# 1st_layer.net
KiCad netlist of a schematic drawn in EAGLE
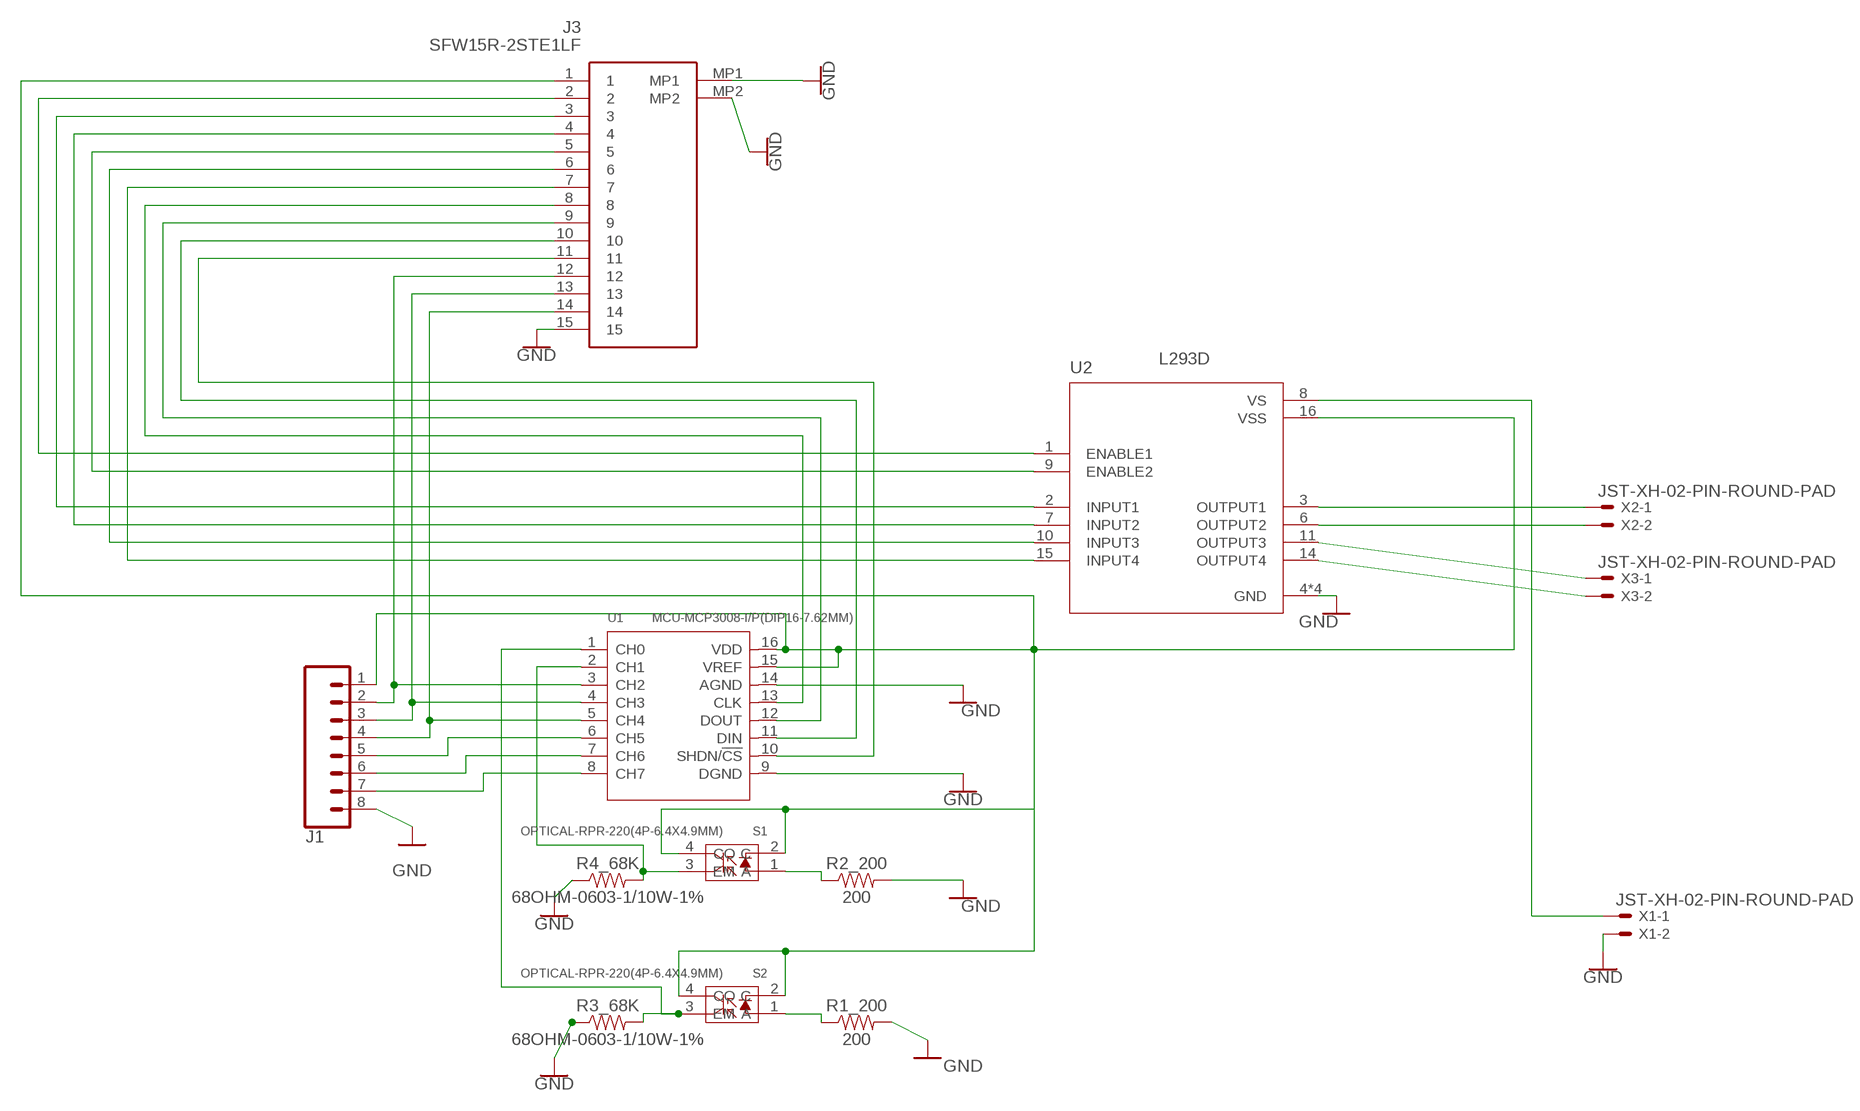
[diagram p0: schematic, sheet 1]

(export (version "E")
  (design (tool "Eeschema 10.0.6"))
  (components
    (comp (ref "J1")
      (value "CONN_08LONGPADS")
      (footprint "eagle-import:1X08_LONGPADS")
      (libsource (lib "eagle-import") (part "CONN_08LONGPADS"))
    )
    (comp (ref "J3")
      (value "SFW15R-2STE1LF")
      (footprint "eagle-import:SFW15R2STE1LF")
      (libsource (lib "eagle-import") (part "SFW15R-2STE1LF"))
    )
    (comp (ref "R1_200")
      (value "200")
      (footprint "eagle-import:0603")
      (libsource (lib "eagle-import") (part "200OHM-0603-1/10W-1%"))
    )
    (comp (ref "R2_200")
      (value "200")
      (footprint "eagle-import:0603")
      (libsource (lib "eagle-import") (part "200OHM-0603-1/10W-1%"))
    )
    (comp (ref "R3_68K")
      (value "68OHM-0603-1/10W-1%")
      (footprint "eagle-import:0603")
      (libsource (lib "eagle-import") (part "68OHM-0603-1/10W-1%"))
    )
    (comp (ref "R4_68K")
      (value "68OHM-0603-1/10W-1%")
      (footprint "eagle-import:0603")
      (libsource (lib "eagle-import") (part "68OHM-0603-1/10W-1%"))
    )
    (comp (ref "S1")
      (value "OPTICAL-RPR-220(4P-6.4X4.9MM)")
      (footprint "eagle-import:SNR4-8.7X4.5X5.8MM")
      (fields
        (field (name "DIGI-KEY_PART_NUMBER") "511-1366-ND")
        (field (name "MF") "Rohm")
        (field (name "MP") "RPR-220")
      )
      (libsource (lib "eagle-import") (part "OPTICAL-RPR-220(4P-6.4X4.9MM)"))
    )
    (comp (ref "S2")
      (value "OPTICAL-RPR-220(4P-6.4X4.9MM)")
      (footprint "eagle-import:SNR4-8.7X4.5X5.8MM")
      (fields
        (field (name "DIGI-KEY_PART_NUMBER") "511-1366-ND")
        (field (name "MF") "Rohm")
        (field (name "MP") "RPR-220")
      )
      (libsource (lib "eagle-import") (part "OPTICAL-RPR-220(4P-6.4X4.9MM)"))
    )
    (comp (ref "U1")
      (value "MCU-MCP3008-I/P(DIP16-7.62MM)")
      (footprint "eagle-import:DIP16-2.54-19.2X7.62MM")
      (fields (field (name "MF") "Microchip") (field (name "MP") "MCP3008-I/P"))
      (libsource (lib "eagle-import") (part "MCU-MCP3008-I/P(DIP16-7.62MM)"))
    )
    (comp (ref "U2")
      (value "L293D")
      (footprint "eagle-import:DIP880W50P254L2000H510Q16")
      (fields (field (name "MF") "STMicroelectronics"))
      (libsource (lib "eagle-import") (part "L293D"))
    )
    (comp (ref "X1")
      (value "JST-XH-02-PIN-ROUND-PAD")
      (footprint "eagle-import:JST-XH-02-PACKAGE-ROUND-PAD")
      (libsource (lib "eagle-import") (part "JST-XH-02-PIN-ROUND-PAD"))
    )
    (comp (ref "X2")
      (value "JST-XH-02-PIN-ROUND-PAD")
      (footprint "eagle-import:JST-XH-02-PACKAGE-ROUND-PAD")
      (libsource (lib "eagle-import") (part "JST-XH-02-PIN-ROUND-PAD"))
    )
    (comp (ref "X3")
      (value "JST-XH-02-PIN-ROUND-PAD")
      (footprint "eagle-import:JST-XH-02-PACKAGE-ROUND-PAD")
      (libsource (lib "eagle-import") (part "JST-XH-02-PIN-ROUND-PAD"))
    )
  )
  (nets
    (net (code "1") (name "GND") (class "Default")
      (node (ref "J1") (pin "8") (pinfunction "8_8") (pintype "passive"))
      (node (ref "J3") (pin "15") (pinfunction "15_15") (pintype "bidirectional"))
      (node (ref "J3") (pin "MP1") (pinfunction "MP1_MP1") (pintype "bidirectional"))
      (node (ref "J3") (pin "MP2") (pinfunction "MP2_MP2") (pintype "bidirectional"))
      (node (ref "R1_200") (pin "2") (pinfunction "2_2") (pintype "passive"))
      (node (ref "R2_200") (pin "2") (pinfunction "2_2") (pintype "passive"))
      (node (ref "R3_68K") (pin "1") (pinfunction "1_1") (pintype "passive"))
      (node (ref "R4_68K") (pin "1") (pinfunction "1_1") (pintype "passive"))
      (node (ref "U1") (pin "14") (pinfunction "AGND_14") (pintype "input"))
      (node (ref "U1") (pin "9") (pinfunction "DGND_9") (pintype "output"))
      (node (ref "U2") (pin "12") (pinfunction "GND_12") (pintype "power_in"))
      (node (ref "U2") (pin "13") (pinfunction "GND_13") (pintype "power_in"))
      (node (ref "U2") (pin "4") (pinfunction "GND_4") (pintype "power_in"))
      (node (ref "U2") (pin "5") (pinfunction "GND_5") (pintype "power_in"))
      (node (ref "X1") (pin "2") (pinfunction "S_2") (pintype "passive"))
    )
    (net (code "2") (name "Net-(S1-A)") (class "Default")
      (node (ref "R2_200") (pin "1") (pinfunction "1_1") (pintype "passive"))
      (node (ref "S1") (pin "1") (pinfunction "A_1") (pintype "bidirectional"))
    )
    (net (code "3") (name "Net-(S1-C)") (class "Default")
      (node (ref "J1") (pin "1") (pinfunction "1_1") (pintype "passive"))
      (node (ref "J3") (pin "1") (pinfunction "1_1") (pintype "bidirectional"))
      (node (ref "S1") (pin "2") (pinfunction "C_2") (pintype "bidirectional"))
      (node (ref "S1") (pin "4") (pinfunction "CO_4") (pintype "bidirectional"))
      (node (ref "S2") (pin "2") (pinfunction "C_2") (pintype "bidirectional"))
      (node (ref "S2") (pin "4") (pinfunction "CO_4") (pintype "bidirectional"))
      (node (ref "U1") (pin "15") (pinfunction "VREF_15") (pintype "input"))
      (node (ref "U1") (pin "16") (pinfunction "VDD_16") (pintype "power_in"))
      (node (ref "U2") (pin "16") (pinfunction "VSS_16") (pintype "power_in"))
    )
    (net (code "4") (name "Net-(S1-EM)") (class "Default")
      (node (ref "R4_68K") (pin "2") (pinfunction "2_2") (pintype "passive"))
      (node (ref "S1") (pin "3") (pinfunction "EM_3") (pintype "bidirectional"))
      (node (ref "U1") (pin "2") (pinfunction "CH1_2") (pintype "input"))
    )
    (net (code "5") (name "Net-(S2-A)") (class "Default")
      (node (ref "R1_200") (pin "1") (pinfunction "1_1") (pintype "passive"))
      (node (ref "S2") (pin "1") (pinfunction "A_1") (pintype "bidirectional"))
    )
    (net (code "6") (name "Net-(S2-EM)") (class "Default")
      (node (ref "R3_68K") (pin "2") (pinfunction "2_2") (pintype "passive"))
      (node (ref "S2") (pin "3") (pinfunction "EM_3") (pintype "bidirectional"))
      (node (ref "U1") (pin "1") (pinfunction "CH0_1") (pintype "output"))
    )
    (net (code "7") (name "Net-(U1-CH2)") (class "Default")
      (node (ref "J1") (pin "2") (pinfunction "2_2") (pintype "passive"))
      (node (ref "J3") (pin "12") (pinfunction "12_12") (pintype "bidirectional"))
      (node (ref "U1") (pin "3") (pinfunction "CH2_3") (pintype "output"))
    )
    (net (code "8") (name "Net-(U1-CH3)") (class "Default")
      (node (ref "J1") (pin "3") (pinfunction "3_3") (pintype "passive"))
      (node (ref "J3") (pin "13") (pinfunction "13_13") (pintype "bidirectional"))
      (node (ref "U1") (pin "4") (pinfunction "CH3_4") (pintype "input"))
    )
    (net (code "9") (name "Net-(U1-CH4)") (class "Default")
      (node (ref "J1") (pin "4") (pinfunction "4_4") (pintype "passive"))
      (node (ref "J3") (pin "14") (pinfunction "14_14") (pintype "bidirectional"))
      (node (ref "U1") (pin "5") (pinfunction "CH4_5") (pintype "input"))
    )
    (net (code "10") (name "Net-(U1-CH5)") (class "Default")
      (node (ref "J1") (pin "5") (pinfunction "5_5") (pintype "passive"))
      (node (ref "U1") (pin "6") (pinfunction "CH5_6") (pintype "input"))
    )
    (net (code "11") (name "Net-(U1-CH6)") (class "Default")
      (node (ref "J1") (pin "6") (pinfunction "6_6") (pintype "passive"))
      (node (ref "U1") (pin "7") (pinfunction "CH6_7") (pintype "output"))
    )
    (net (code "12") (name "Net-(U1-CH7)") (class "Default")
      (node (ref "J1") (pin "7") (pinfunction "7_7") (pintype "passive"))
      (node (ref "U1") (pin "8") (pinfunction "CH7_8") (pintype "input"))
    )
    (net (code "13") (name "Net-(U1-CLK)") (class "Default")
      (node (ref "J3") (pin "8") (pinfunction "8_8") (pintype "bidirectional"))
      (node (ref "U1") (pin "13") (pinfunction "CLK_13") (pintype "output"))
    )
    (net (code "14") (name "Net-(U1-DIN)") (class "Default")
      (node (ref "J3") (pin "10") (pinfunction "10_10") (pintype "bidirectional"))
      (node (ref "U1") (pin "11") (pinfunction "DIN_11") (pintype "input"))
    )
    (net (code "15") (name "Net-(U1-DOUT)") (class "Default")
      (node (ref "J3") (pin "9") (pinfunction "9_9") (pintype "bidirectional"))
      (node (ref "U1") (pin "12") (pinfunction "DOUT_12") (pintype "input"))
    )
    (net (code "16") (name "Net-(U1-SHDN{slash}~{CS})") (class "Default")
      (node (ref "J3") (pin "11") (pinfunction "11_11") (pintype "bidirectional"))
      (node (ref "U1") (pin "10") (pinfunction "SHDN/~{CS}_10") (pintype "output"))
    )
    (net (code "17") (name "Net-(U2-ENABLE1)") (class "Default")
      (node (ref "J3") (pin "2") (pinfunction "2_2") (pintype "bidirectional"))
      (node (ref "U2") (pin "1") (pinfunction "ENABLE1_1") (pintype "input"))
    )
    (net (code "18") (name "Net-(U2-ENABLE2)") (class "Default")
      (node (ref "J3") (pin "5") (pinfunction "5_5") (pintype "bidirectional"))
      (node (ref "U2") (pin "9") (pinfunction "ENABLE2_9") (pintype "input"))
    )
    (net (code "19") (name "Net-(U2-INPUT1)") (class "Default")
      (node (ref "J3") (pin "3") (pinfunction "3_3") (pintype "bidirectional"))
      (node (ref "U2") (pin "2") (pinfunction "INPUT1_2") (pintype "input"))
    )
    (net (code "20") (name "Net-(U2-INPUT2)") (class "Default")
      (node (ref "J3") (pin "4") (pinfunction "4_4") (pintype "bidirectional"))
      (node (ref "U2") (pin "7") (pinfunction "INPUT2_7") (pintype "input"))
    )
    (net (code "21") (name "Net-(U2-INPUT3)") (class "Default")
      (node (ref "J3") (pin "6") (pinfunction "6_6") (pintype "bidirectional"))
      (node (ref "U2") (pin "10") (pinfunction "INPUT3_10") (pintype "input"))
    )
    (net (code "22") (name "Net-(U2-INPUT4)") (class "Default")
      (node (ref "J3") (pin "7") (pinfunction "7_7") (pintype "bidirectional"))
      (node (ref "U2") (pin "15") (pinfunction "INPUT4_15") (pintype "input"))
    )
    (net (code "23") (name "Net-(U2-OUTPUT1)") (class "Default")
      (node (ref "U2") (pin "3") (pinfunction "OUTPUT1_3") (pintype "output"))
      (node (ref "X2") (pin "1") (pinfunction "S_1") (pintype "passive"))
    )
    (net (code "24") (name "Net-(U2-OUTPUT2)") (class "Default")
      (node (ref "U2") (pin "6") (pinfunction "OUTPUT2_6") (pintype "output"))
      (node (ref "X2") (pin "2") (pinfunction "S_2") (pintype "passive"))
    )
    (net (code "25") (name "Net-(U2-OUTPUT3)") (class "Default")
      (node (ref "U2") (pin "11") (pinfunction "OUTPUT3_11") (pintype "output"))
      (node (ref "X3") (pin "1") (pinfunction "S_1") (pintype "passive"))
    )
    (net (code "26") (name "Net-(U2-OUTPUT4)") (class "Default")
      (node (ref "U2") (pin "14") (pinfunction "OUTPUT4_14") (pintype "output"))
      (node (ref "X3") (pin "2") (pinfunction "S_2") (pintype "passive"))
    )
    (net (code "27") (name "Net-(U2-VS)") (class "Default")
      (node (ref "U2") (pin "8") (pinfunction "VS_8") (pintype "power_in"))
      (node (ref "X1") (pin "1") (pinfunction "S_1") (pintype "passive"))
    )
  )
)
